# SparkFun_ACS723_Current_Sensor_Breakout.net
KiCad netlist of a schematic drawn in EAGLE
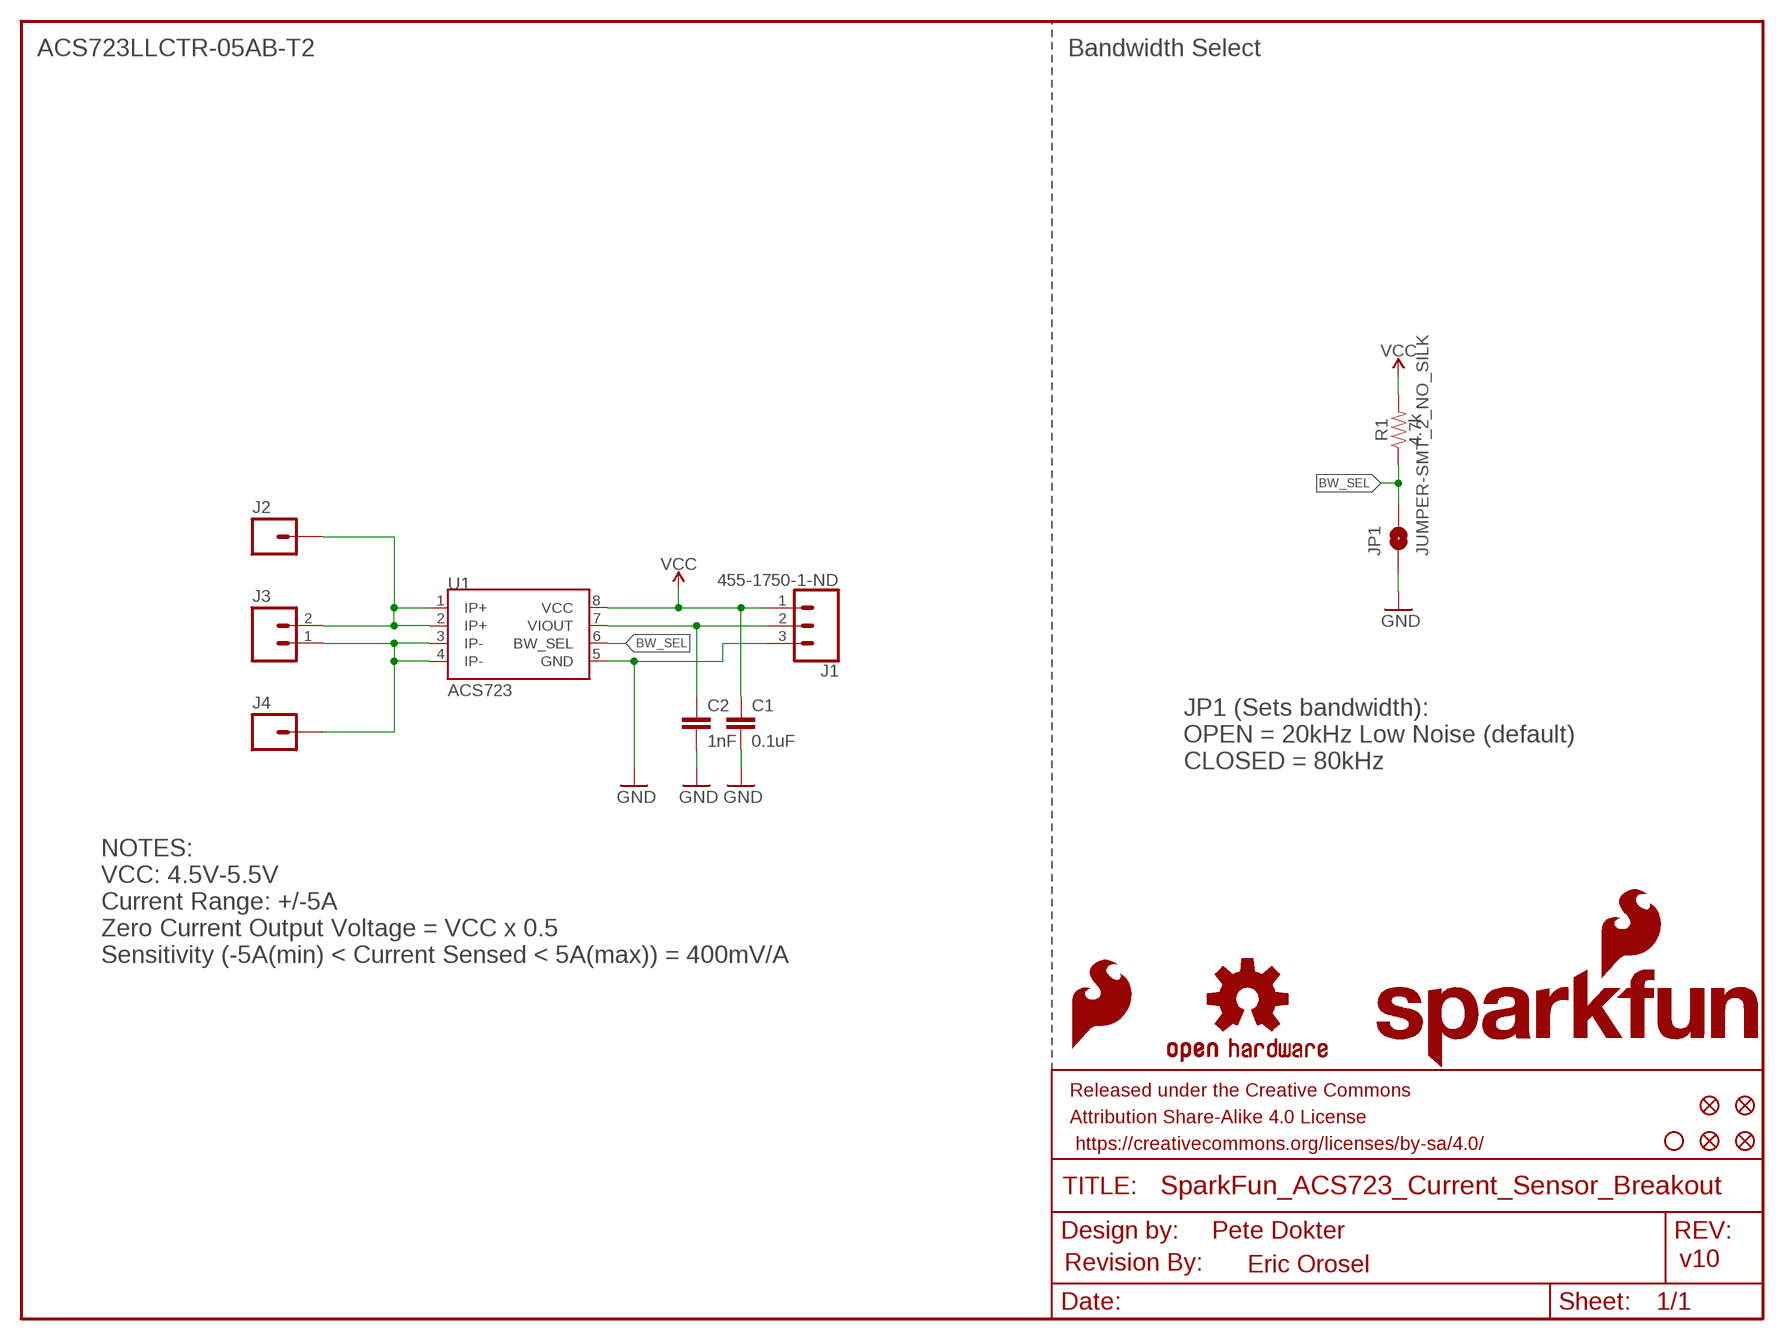
[diagram p0: schematic, sheet 1]

(export (version "E")
  (design (tool "Eeschema 10.0.6"))
  (components
    (comp (ref "C1")
      (value "0.1uF")
      (footprint "eagle-import:0603")
      (libsource (lib "eagle-import") (part "0.1UF-0603-25V-(+80/-20%)"))
    )
    (comp (ref "C2")
      (value "1nF")
      (footprint "eagle-import:0603")
      (libsource (lib "eagle-import") (part "1.0NF/1000PF-0603-50V-10%"))
    )
    (comp (ref "FD2")
      (value "FIDUCIAL1X2")
      (footprint "eagle-import:FIDUCIAL-1X2")
      (libsource (lib "eagle-import") (part "FIDUCIAL1X2"))
    )
    (comp (ref "FD3")
      (value "FIDUCIAL1X2")
      (footprint "eagle-import:FIDUCIAL-1X2")
      (libsource (lib "eagle-import") (part "FIDUCIAL1X2"))
    )
    (comp (ref "FD4")
      (value "FIDUCIAL1X2")
      (footprint "eagle-import:FIDUCIAL-1X2")
      (libsource (lib "eagle-import") (part "FIDUCIAL1X2"))
    )
    (comp (ref "FD5")
      (value "FIDUCIAL1X2")
      (footprint "eagle-import:FIDUCIAL-1X2")
      (libsource (lib "eagle-import") (part "FIDUCIAL1X2"))
    )
    (comp (ref "FRAME1")
      (value "FRAME-LETTER")
      (footprint "eagle-import:CREATIVE_COMMONS")
      (libsource (lib "eagle-import") (part "FRAME-LETTER"))
    )
    (comp (ref "J1")
      (value "455-1750-1-ND")
      (footprint "eagle-import:1X03")
      (libsource (lib "eagle-import") (part "CONN_03"))
    )
    (comp (ref "J2")
      (value "M01-SMTSO-256-ET")
      (footprint "eagle-import:SMTSO-256-ET")
      (libsource (lib "eagle-import") (part "M01-SMTSO-256-ET"))
    )
    (comp (ref "J3")
      (value "M021X02_NO_SILK")
      (footprint "eagle-import:1X02_NO_SILK@1")
      (libsource (lib "eagle-import") (part "M021X02_NO_SILK"))
    )
    (comp (ref "J4")
      (value "M01-SMTSO-256-ET")
      (footprint "eagle-import:SMTSO-256-ET")
      (libsource (lib "eagle-import") (part "M01-SMTSO-256-ET"))
    )
    (comp (ref "JP1")
      (value "JUMPER-SMT_2_NO_SILK")
      (footprint "eagle-import:SMT-JUMPER_2_NO_SILK")
      (libsource (lib "eagle-import") (part "JUMPER-SMT_2_NO_SILK"))
    )
    (comp (ref "JP3")
      (value "STAND-OFFTIGHT")
      (footprint "eagle-import:STAND-OFF-TIGHT")
      (libsource (lib "eagle-import") (part "STAND-OFFTIGHT"))
    )
    (comp (ref "LOGO1")
      (value "SFE_LOGO_FLAME.1_INCH")
      (footprint "eagle-import:SFE_LOGO_FLAME_.1")
      (libsource (lib "eagle-import") (part "SFE_LOGO_FLAME.1_INCH"))
    )
    (comp (ref "LOGO3")
      (value "SFE_LOGO_NAME_FLAME.1_INCH")
      (footprint "eagle-import:SFE_LOGO_NAME_FLAME_.1")
      (libsource (lib "eagle-import") (part "SFE_LOGO_NAME_FLAME.1_INCH"))
    )
    (comp (ref "LOGO4")
      (value "OSHW-LOGOM")
      (footprint "eagle-import:OSHW-LOGO-M")
      (libsource (lib "eagle-import") (part "OSHW-LOGOM"))
    )
    (comp (ref "R1")
      (value "4.7k")
      (footprint "eagle-import:0603")
      (libsource (lib "eagle-import") (part "4.7KOHM-0603-1/10W-1%"))
    )
    (comp (ref "U$1")
      (value "REVISION")
      (footprint "eagle-import:REVISION")
      (libsource (lib "eagle-import") (part "REVISION"))
    )
    (comp (ref "U1")
      (value "ACS723")
      (footprint "eagle-import:SO08")
      (fields (field (name "PART_#") "ACS723ACS723LLCTR-05AB-T2"))
      (libsource (lib "eagle-import") (part "ACS723"))
    )
  )
  (nets
    (net (code "1") (name "BW_SEL") (class "Default")
      (node (ref "JP1") (pin "2") (pinfunction "2_2") (pintype "passive"))
      (node (ref "R1") (pin "1") (pinfunction "1_1") (pintype "passive"))
      (node (ref "U1") (pin "6") (pinfunction "BW_SEL_6") (pintype "bidirectional"))
    )
    (net (code "2") (name "GND") (class "Default")
      (node (ref "C1") (pin "2") (pinfunction "2_2") (pintype "passive"))
      (node (ref "C2") (pin "2") (pinfunction "2_2") (pintype "passive"))
      (node (ref "J1") (pin "3") (pinfunction "3_3") (pintype "passive"))
      (node (ref "JP1") (pin "1") (pinfunction "1_1") (pintype "passive"))
      (node (ref "U1") (pin "5") (pinfunction "GND_5") (pintype "bidirectional"))
    )
    (net (code "3") (name "Net-(J2-1)") (class "Default")
      (node (ref "J2") (pin "P$1") (pinfunction "1_P$1") (pintype "passive"))
      (node (ref "J3") (pin "2") (pinfunction "2_2") (pintype "passive"))
      (node (ref "U1") (pin "1") (pinfunction "IP+_1") (pintype "input"))
      (node (ref "U1") (pin "2") (pinfunction "IP+_2") (pintype "input"))
    )
    (net (code "4") (name "Net-(J4-1)") (class "Default")
      (node (ref "J3") (pin "1") (pinfunction "1_1") (pintype "passive"))
      (node (ref "J4") (pin "P$1") (pinfunction "1_P$1") (pintype "passive"))
      (node (ref "U1") (pin "3") (pinfunction "IP-_3") (pintype "bidirectional"))
      (node (ref "U1") (pin "4") (pinfunction "IP-_4") (pintype "bidirectional"))
    )
    (net (code "5") (name "Net-(U1-VIOUT)") (class "Default")
      (node (ref "C2") (pin "1") (pinfunction "1_1") (pintype "passive"))
      (node (ref "J1") (pin "2") (pinfunction "2_2") (pintype "passive"))
      (node (ref "U1") (pin "7") (pinfunction "VIOUT_7") (pintype "bidirectional"))
    )
    (net (code "6") (name "VCC") (class "Default")
      (node (ref "C1") (pin "1") (pinfunction "1_1") (pintype "passive"))
      (node (ref "J1") (pin "1") (pinfunction "1_1") (pintype "passive"))
      (node (ref "R1") (pin "2") (pinfunction "2_2") (pintype "passive"))
      (node (ref "U1") (pin "8") (pinfunction "VCC_8") (pintype "bidirectional"))
    )
  )
)
